# A203-V2-Expansion-Board.net
KiCad netlist of a schematic drawn in EAGLE
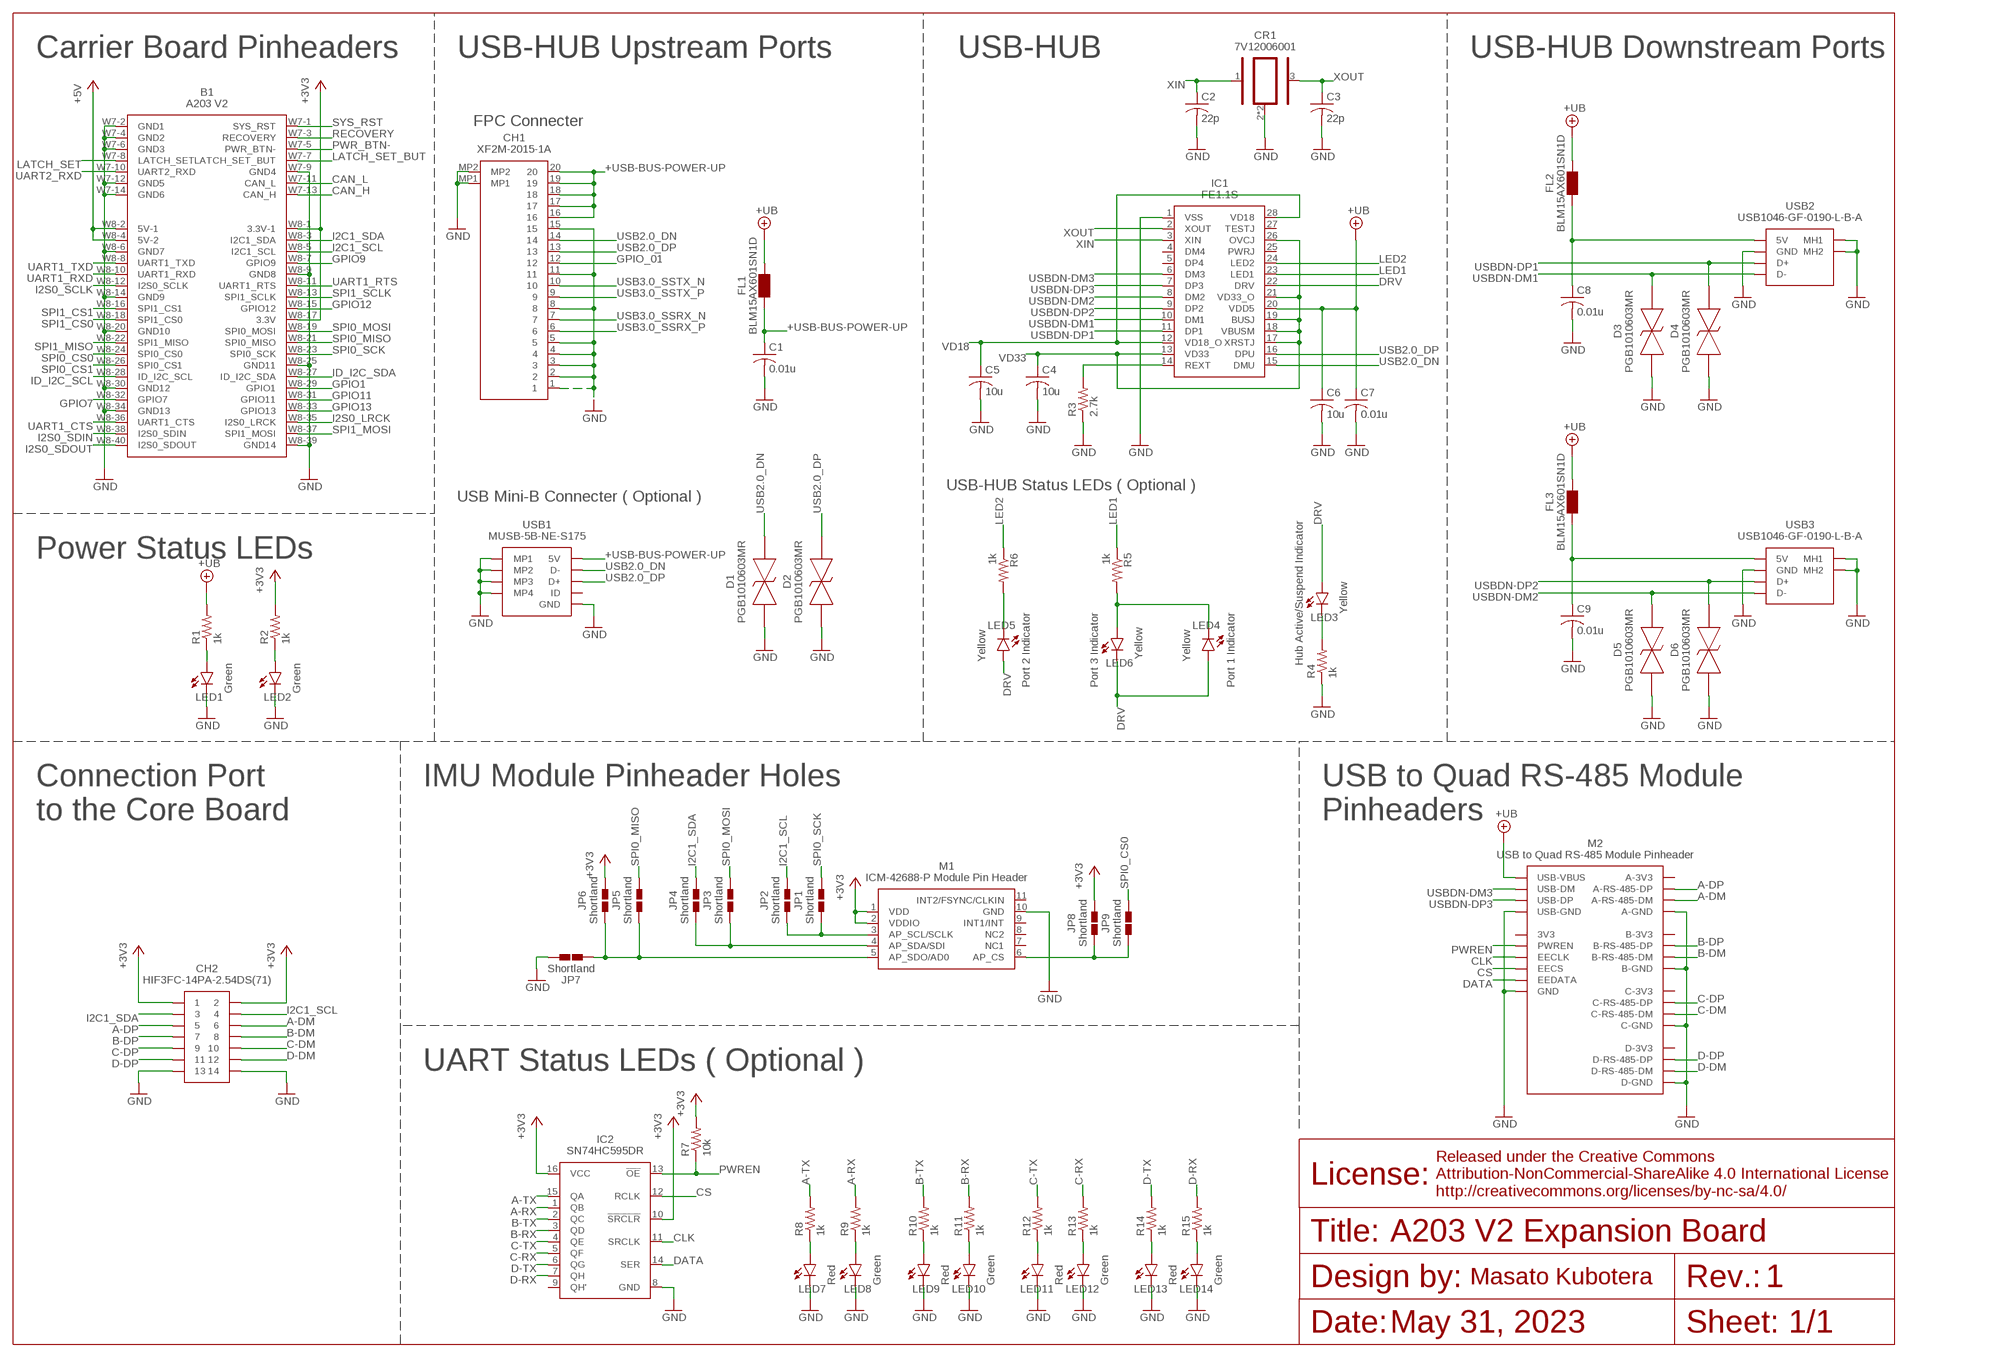
[diagram p0: schematic, sheet 1]

(export (version "E")
  (design (tool "Eeschema 10.0.6"))
  (components
    (comp (ref "B1")
      (value "SEEED_A207_V2")
      (footprint "eagle-import:SEEED_A203_V2")
      (libsource (lib "eagle-import") (part "SEEED_A207_V2"))
    )
    (comp (ref "C1")
      (value "0.01u")
      (footprint "eagle-import:C0603")
      (libsource (lib "eagle-import") (part "C-USC0603"))
    )
    (comp (ref "C2")
      (value "22p")
      (footprint "eagle-import:C0603")
      (libsource (lib "eagle-import") (part "C-USC0603"))
    )
    (comp (ref "C3")
      (value "22p")
      (footprint "eagle-import:C0603")
      (libsource (lib "eagle-import") (part "C-USC0603"))
    )
    (comp (ref "C4")
      (value "10u")
      (footprint "eagle-import:C0603")
      (libsource (lib "eagle-import") (part "C-USC0603"))
    )
    (comp (ref "C5")
      (value "10u")
      (footprint "eagle-import:C0603")
      (libsource (lib "eagle-import") (part "C-USC0603"))
    )
    (comp (ref "C6")
      (value "10u")
      (footprint "eagle-import:C0603")
      (libsource (lib "eagle-import") (part "C-USC0603"))
    )
    (comp (ref "C7")
      (value "0.01u")
      (footprint "eagle-import:C0603")
      (libsource (lib "eagle-import") (part "C-USC0603"))
    )
    (comp (ref "C8")
      (value "0.01u")
      (footprint "eagle-import:C0603")
      (libsource (lib "eagle-import") (part "C-USC0603"))
    )
    (comp (ref "C9")
      (value "0.01u")
      (footprint "eagle-import:C0603")
      (libsource (lib "eagle-import") (part "C-USC0603"))
    )
    (comp (ref "CH1")
      (value "XF2M-2015-1A")
      (footprint "eagle-import:XF2M-2015-1A")
      (libsource (lib "eagle-import") (part "XF2M-2015-1A"))
    )
    (comp (ref "CH2")
      (value "HIF3FC-14PA-2.54DS(71)")
      (footprint "eagle-import:HIF3FC-14PA-2.54DS(71)")
      (libsource (lib "eagle-import") (part "HIF3FC-14PA-2.54DS(71)"))
    )
    (comp (ref "CR1")
      (value "7V12006001")
      (footprint "eagle-import:7V12006001")
      (libsource (lib "eagle-import") (part "7V12006001"))
    )
    (comp (ref "D1")
      (value "PGB1010603MR")
      (footprint "eagle-import:0603")
      (libsource (lib "eagle-import") (part "PGB1010603MR"))
    )
    (comp (ref "D2")
      (value "PGB1010603MR")
      (footprint "eagle-import:0603")
      (libsource (lib "eagle-import") (part "PGB1010603MR"))
    )
    (comp (ref "D3")
      (value "PGB1010603MR")
      (footprint "eagle-import:0603")
      (libsource (lib "eagle-import") (part "PGB1010603MR"))
    )
    (comp (ref "D4")
      (value "PGB1010603MR")
      (footprint "eagle-import:0603")
      (libsource (lib "eagle-import") (part "PGB1010603MR"))
    )
    (comp (ref "D5")
      (value "PGB1010603MR")
      (footprint "eagle-import:0603")
      (libsource (lib "eagle-import") (part "PGB1010603MR"))
    )
    (comp (ref "D6")
      (value "PGB1010603MR")
      (footprint "eagle-import:0603")
      (libsource (lib "eagle-import") (part "PGB1010603MR"))
    )
    (comp (ref "FL1")
      (value "BLM15AX601SN1D")
      (footprint "eagle-import:BLM15AX601SN1D")
      (libsource (lib "eagle-import") (part "BLM15AX601SN1D"))
    )
    (comp (ref "FL2")
      (value "BLM15AX601SN1D")
      (footprint "eagle-import:BLM15AX601SN1D")
      (libsource (lib "eagle-import") (part "BLM15AX601SN1D"))
    )
    (comp (ref "FL3")
      (value "BLM15AX601SN1D")
      (footprint "eagle-import:BLM15AX601SN1D")
      (libsource (lib "eagle-import") (part "BLM15AX601SN1D"))
    )
    (comp (ref "IC1")
      (value "FE1.1S")
      (footprint "eagle-import:FE1.1S")
      (libsource (lib "eagle-import") (part "FE1.1S"))
    )
    (comp (ref "IC2")
      (value "SN74HC595DR")
      (footprint "eagle-import:SOIC-16")
      (libsource (lib "eagle-import") (part "SN74HC595DR"))
    )
    (comp (ref "JP1")
      (value "SHORTLAND")
      (footprint "eagle-import:SHORTLAND")
      (libsource (lib "eagle-import") (part "SHORTLAND"))
    )
    (comp (ref "JP2")
      (value "SHORTLAND")
      (footprint "eagle-import:SHORTLAND")
      (libsource (lib "eagle-import") (part "SHORTLAND"))
    )
    (comp (ref "JP3")
      (value "SHORTLAND")
      (footprint "eagle-import:SHORTLAND")
      (libsource (lib "eagle-import") (part "SHORTLAND"))
    )
    (comp (ref "JP4")
      (value "SHORTLAND")
      (footprint "eagle-import:SHORTLAND")
      (libsource (lib "eagle-import") (part "SHORTLAND"))
    )
    (comp (ref "JP5")
      (value "SHORTLAND")
      (footprint "eagle-import:SHORTLAND")
      (libsource (lib "eagle-import") (part "SHORTLAND"))
    )
    (comp (ref "JP6")
      (value "SHORTLAND")
      (footprint "eagle-import:SHORTLAND")
      (libsource (lib "eagle-import") (part "SHORTLAND"))
    )
    (comp (ref "JP7")
      (value "SHORTLAND")
      (footprint "eagle-import:SHORTLAND")
      (libsource (lib "eagle-import") (part "SHORTLAND"))
    )
    (comp (ref "JP8")
      (value "SHORTLAND")
      (footprint "eagle-import:SHORTLAND")
      (libsource (lib "eagle-import") (part "SHORTLAND"))
    )
    (comp (ref "JP9")
      (value "SHORTLAND")
      (footprint "eagle-import:SHORTLAND")
      (libsource (lib "eagle-import") (part "SHORTLAND"))
    )
    (comp (ref "LED1")
      (value "Green")
      (footprint "eagle-import:SML0603")
      (libsource (lib "eagle-import") (part "LEDSML0603"))
    )
    (comp (ref "LED2")
      (value "Green")
      (footprint "eagle-import:SML0603")
      (libsource (lib "eagle-import") (part "LEDSML0603"))
    )
    (comp (ref "LED3")
      (value "Yellow")
      (footprint "eagle-import:SML0603")
      (libsource (lib "eagle-import") (part "LEDSML0603"))
    )
    (comp (ref "LED4")
      (value "Yellow")
      (footprint "eagle-import:SML0603")
      (libsource (lib "eagle-import") (part "LEDSML0603"))
    )
    (comp (ref "LED5")
      (value "Yellow")
      (footprint "eagle-import:SML0603")
      (libsource (lib "eagle-import") (part "LEDSML0603"))
    )
    (comp (ref "LED6")
      (value "Yellow")
      (footprint "eagle-import:SML0603")
      (libsource (lib "eagle-import") (part "LEDSML0603"))
    )
    (comp (ref "LED7")
      (value "Red")
      (footprint "eagle-import:SML0603")
      (libsource (lib "eagle-import") (part "LEDSML0603"))
    )
    (comp (ref "LED8")
      (value "Green")
      (footprint "eagle-import:SML0603")
      (libsource (lib "eagle-import") (part "LEDSML0603"))
    )
    (comp (ref "LED9")
      (value "Red")
      (footprint "eagle-import:SML0603")
      (libsource (lib "eagle-import") (part "LEDSML0603"))
    )
    (comp (ref "LED10")
      (value "Green")
      (footprint "eagle-import:SML0603")
      (libsource (lib "eagle-import") (part "LEDSML0603"))
    )
    (comp (ref "LED11")
      (value "Red")
      (footprint "eagle-import:SML0603")
      (libsource (lib "eagle-import") (part "LEDSML0603"))
    )
    (comp (ref "LED12")
      (value "Green")
      (footprint "eagle-import:SML0603")
      (libsource (lib "eagle-import") (part "LEDSML0603"))
    )
    (comp (ref "LED13")
      (value "Red")
      (footprint "eagle-import:SML0603")
      (libsource (lib "eagle-import") (part "LEDSML0603"))
    )
    (comp (ref "LED14")
      (value "Green")
      (footprint "eagle-import:SML0603")
      (libsource (lib "eagle-import") (part "LEDSML0603"))
    )
    (comp (ref "M1")
      (value "ICM-42688-P-MODULE-PINHEADER")
      (footprint "eagle-import:ICM-42688-P-MODULE-PINHEADER")
      (libsource (lib "eagle-import") (part "ICM-42688-P-MODULE-PINHEADER"))
    )
    (comp (ref "M2")
      (value "USB-TO-QUAD-RS-485-CONV-MODULET-PLACE")
      (footprint "eagle-import:USB-TO-QUAD-RS-485-CONV-MODULE-SILK")
      (libsource (lib "eagle-import") (part "USB-TO-QUAD-RS-485-CONV-MODULET-PLACE"))
    )
    (comp (ref "R1")
      (value "1k")
      (footprint "eagle-import:R0603")
      (libsource (lib "eagle-import") (part "R-US_R0603"))
    )
    (comp (ref "R2")
      (value "1k")
      (footprint "eagle-import:R0603")
      (libsource (lib "eagle-import") (part "R-US_R0603"))
    )
    (comp (ref "R3")
      (value "2.7k")
      (footprint "eagle-import:R0603")
      (libsource (lib "eagle-import") (part "R-US_R0603"))
    )
    (comp (ref "R4")
      (value "1k")
      (footprint "eagle-import:R0603")
      (libsource (lib "eagle-import") (part "R-US_R0603"))
    )
    (comp (ref "R5")
      (value "1k")
      (footprint "eagle-import:R0603")
      (libsource (lib "eagle-import") (part "R-US_R0603"))
    )
    (comp (ref "R6")
      (value "1k")
      (footprint "eagle-import:R0603")
      (libsource (lib "eagle-import") (part "R-US_R0603"))
    )
    (comp (ref "R7")
      (value "10k")
      (footprint "eagle-import:R0603")
      (libsource (lib "eagle-import") (part "R-US_R0603"))
    )
    (comp (ref "R8")
      (value "1k")
      (footprint "eagle-import:R0603")
      (libsource (lib "eagle-import") (part "R-US_R0603"))
    )
    (comp (ref "R9")
      (value "1k")
      (footprint "eagle-import:R0603")
      (libsource (lib "eagle-import") (part "R-US_R0603"))
    )
    (comp (ref "R10")
      (value "1k")
      (footprint "eagle-import:R0603")
      (libsource (lib "eagle-import") (part "R-US_R0603"))
    )
    (comp (ref "R11")
      (value "1k")
      (footprint "eagle-import:R0603")
      (libsource (lib "eagle-import") (part "R-US_R0603"))
    )
    (comp (ref "R12")
      (value "1k")
      (footprint "eagle-import:R0603")
      (libsource (lib "eagle-import") (part "R-US_R0603"))
    )
    (comp (ref "R13")
      (value "1k")
      (footprint "eagle-import:R0603")
      (libsource (lib "eagle-import") (part "R-US_R0603"))
    )
    (comp (ref "R14")
      (value "1k")
      (footprint "eagle-import:R0603")
      (libsource (lib "eagle-import") (part "R-US_R0603"))
    )
    (comp (ref "R15")
      (value "1k")
      (footprint "eagle-import:R0603")
      (libsource (lib "eagle-import") (part "R-US_R0603"))
    )
    (comp (ref "USB1")
      (value "MINI_USB_B_SMD")
      (footprint "eagle-import:MINI_USB_B_SMD")
      (libsource (lib "eagle-import") (part "MINI_USB_B_SMD"))
    )
    (comp (ref "USB2")
      (value "USB_A_X1_SMD")
      (footprint "eagle-import:USB_A_X1_SMD")
      (libsource (lib "eagle-import") (part "USB_A_X1_SMD"))
    )
    (comp (ref "USB3")
      (value "USB_A_X1_SMD")
      (footprint "eagle-import:USB_A_X1_SMD")
      (libsource (lib "eagle-import") (part "USB_A_X1_SMD"))
    )
  )
  (nets
    (net (code "1") (name "+3V3") (class "Default")
      (node (ref "B1") (pin "W8-1") (pinfunction "3.3V-1_W8-1") (pintype "bidirectional"))
      (node (ref "B1") (pin "W8-17") (pinfunction "3.3V_W8-17") (pintype "bidirectional"))
      (node (ref "CH2") (pin "1") (pinfunction "1_1") (pintype "bidirectional"))
      (node (ref "CH2") (pin "2") (pinfunction "2_2") (pintype "bidirectional"))
      (node (ref "IC2") (pin "10") (pinfunction "~{SRCLR}_10") (pintype "bidirectional"))
      (node (ref "IC2") (pin "16") (pinfunction "VCC_16") (pintype "bidirectional"))
      (node (ref "JP6") (pin "2") (pinfunction "2_2") (pintype "bidirectional"))
      (node (ref "JP8") (pin "2") (pinfunction "2_2") (pintype "bidirectional"))
      (node (ref "M1") (pin "1") (pinfunction "VDD_1") (pintype "bidirectional"))
      (node (ref "M1") (pin "2") (pinfunction "VDDIO_2") (pintype "bidirectional"))
      (node (ref "R2") (pin "2") (pinfunction "2_2") (pintype "passive"))
      (node (ref "R7") (pin "2") (pinfunction "2_2") (pintype "passive"))
    )
    (net (code "2") (name "+5V") (class "Default")
      (node (ref "B1") (pin "W8-2") (pinfunction "5V-1_W8-2") (pintype "bidirectional"))
      (node (ref "B1") (pin "W8-4") (pinfunction "5V-2_W8-4") (pintype "bidirectional"))
    )
    (net (code "3") (name "+UB") (class "Default")
      (node (ref "C6") (pin "1") (pinfunction "1_1") (pintype "passive"))
      (node (ref "C7") (pin "1") (pinfunction "1_1") (pintype "passive"))
      (node (ref "FL1") (pin "2") (pinfunction "2_2") (pintype "bidirectional"))
      (node (ref "FL2") (pin "2") (pinfunction "2_2") (pintype "bidirectional"))
      (node (ref "FL3") (pin "2") (pinfunction "2_2") (pintype "bidirectional"))
      (node (ref "IC1") (pin "20") (pinfunction "VDD5_20") (pintype "bidirectional"))
      (node (ref "M2") (pin "USB-VBUS") (pinfunction "USB-VBUS_USB-VBUS") (pintype "bidirectional"))
      (node (ref "R1") (pin "2") (pinfunction "2_2") (pintype "passive"))
    )
    (net (code "4") (name "/+USB-BUS-POWER-UP") (class "Default")
      (node (ref "C1") (pin "1") (pinfunction "1_1") (pintype "passive"))
      (node (ref "CH1") (pin "16") (pinfunction "16_16") (pintype "bidirectional"))
      (node (ref "CH1") (pin "17") (pinfunction "17_17") (pintype "bidirectional"))
      (node (ref "CH1") (pin "18") (pinfunction "18_18") (pintype "bidirectional"))
      (node (ref "CH1") (pin "19") (pinfunction "19_19") (pintype "bidirectional"))
      (node (ref "CH1") (pin "20") (pinfunction "20_20") (pintype "bidirectional"))
      (node (ref "FL1") (pin "1") (pinfunction "1_1") (pintype "bidirectional"))
      (node (ref "USB1") (pin "1") (pinfunction "5V_1") (pintype "bidirectional"))
    )
    (net (code "5") (name "/A-DM") (class "Default")
      (node (ref "CH2") (pin "6") (pinfunction "6_6") (pintype "bidirectional"))
      (node (ref "M2") (pin "A-RS-485-DM") (pinfunction "A-RS-485-DM_A-RS-485-DM") (pintype "bidirectional"))
    )
    (net (code "6") (name "/A-DP") (class "Default")
      (node (ref "CH2") (pin "5") (pinfunction "5_5") (pintype "bidirectional"))
      (node (ref "M2") (pin "A-RS-485-DP") (pinfunction "A-RS-485-DP_A-RS-485-DP") (pintype "bidirectional"))
    )
    (net (code "7") (name "/A-RX") (class "Default")
      (node (ref "IC2") (pin "1") (pinfunction "QB_1") (pintype "bidirectional"))
      (node (ref "R9") (pin "2") (pinfunction "2_2") (pintype "passive"))
    )
    (net (code "8") (name "/A-TX") (class "Default")
      (node (ref "IC2") (pin "15") (pinfunction "QA_15") (pintype "bidirectional"))
      (node (ref "R8") (pin "2") (pinfunction "2_2") (pintype "passive"))
    )
    (net (code "9") (name "/B-DM") (class "Default")
      (node (ref "CH2") (pin "8") (pinfunction "8_8") (pintype "bidirectional"))
      (node (ref "M2") (pin "B-RS-485-DM") (pinfunction "B-RS-485-DM_B-RS-485-DM") (pintype "bidirectional"))
    )
    (net (code "10") (name "/B-DP") (class "Default")
      (node (ref "CH2") (pin "7") (pinfunction "7_7") (pintype "bidirectional"))
      (node (ref "M2") (pin "B-RS-485-DP") (pinfunction "B-RS-485-DP_B-RS-485-DP") (pintype "bidirectional"))
    )
    (net (code "11") (name "/B-RX") (class "Default")
      (node (ref "IC2") (pin "3") (pinfunction "QD_3") (pintype "bidirectional"))
      (node (ref "R11") (pin "2") (pinfunction "2_2") (pintype "passive"))
    )
    (net (code "12") (name "/B-TX") (class "Default")
      (node (ref "IC2") (pin "2") (pinfunction "QC_2") (pintype "bidirectional"))
      (node (ref "R10") (pin "2") (pinfunction "2_2") (pintype "passive"))
    )
    (net (code "13") (name "/C-DM") (class "Default")
      (node (ref "CH2") (pin "10") (pinfunction "10_10") (pintype "bidirectional"))
      (node (ref "M2") (pin "C-RS-485-DM") (pinfunction "C-RS-485-DM_C-RS-485-DM") (pintype "bidirectional"))
    )
    (net (code "14") (name "/C-DP") (class "Default")
      (node (ref "CH2") (pin "9") (pinfunction "9_9") (pintype "bidirectional"))
      (node (ref "M2") (pin "C-RS-485-DP") (pinfunction "C-RS-485-DP_C-RS-485-DP") (pintype "bidirectional"))
    )
    (net (code "15") (name "/C-RX") (class "Default")
      (node (ref "IC2") (pin "5") (pinfunction "QF_5") (pintype "bidirectional"))
      (node (ref "R13") (pin "2") (pinfunction "2_2") (pintype "passive"))
    )
    (net (code "16") (name "/C-TX") (class "Default")
      (node (ref "IC2") (pin "4") (pinfunction "QE_4") (pintype "bidirectional"))
      (node (ref "R12") (pin "2") (pinfunction "2_2") (pintype "passive"))
    )
    (net (code "17") (name "/CAN_H") (class "Default")
      (node (ref "B1") (pin "W7-13") (pinfunction "CAN_H_W7-13") (pintype "bidirectional"))
    )
    (net (code "18") (name "/CAN_L") (class "Default")
      (node (ref "B1") (pin "W7-11") (pinfunction "CAN_L_W7-11") (pintype "bidirectional"))
    )
    (net (code "19") (name "/CLK") (class "Default")
      (node (ref "IC2") (pin "11") (pinfunction "SRCLK_11") (pintype "bidirectional"))
      (node (ref "M2") (pin "EECLK") (pinfunction "EECLK_EECLK") (pintype "bidirectional"))
    )
    (net (code "20") (name "/CS") (class "Default")
      (node (ref "IC2") (pin "12") (pinfunction "RCLK_12") (pintype "bidirectional"))
      (node (ref "M2") (pin "EECS") (pinfunction "EECS_EECS") (pintype "bidirectional"))
    )
    (net (code "21") (name "/D-DM") (class "Default")
      (node (ref "CH2") (pin "12") (pinfunction "12_12") (pintype "bidirectional"))
      (node (ref "M2") (pin "D-RS-485-DM") (pinfunction "D-RS-485-DM_D-RS-485-DM") (pintype "bidirectional"))
    )
    (net (code "22") (name "/D-DP") (class "Default")
      (node (ref "CH2") (pin "11") (pinfunction "11_11") (pintype "bidirectional"))
      (node (ref "M2") (pin "D-RS-485-DP") (pinfunction "D-RS-485-DP_D-RS-485-DP") (pintype "bidirectional"))
    )
    (net (code "23") (name "/D-RX") (class "Default")
      (node (ref "IC2") (pin "7") (pinfunction "QH_7") (pintype "bidirectional"))
      (node (ref "R15") (pin "2") (pinfunction "2_2") (pintype "passive"))
    )
    (net (code "24") (name "/D-TX") (class "Default")
      (node (ref "IC2") (pin "6") (pinfunction "QG_6") (pintype "bidirectional"))
      (node (ref "R14") (pin "2") (pinfunction "2_2") (pintype "passive"))
    )
    (net (code "25") (name "/DATA") (class "Default")
      (node (ref "IC2") (pin "14") (pinfunction "SER_14") (pintype "bidirectional"))
      (node (ref "M2") (pin "EEDATA") (pinfunction "EEDATA_EEDATA") (pintype "bidirectional"))
    )
    (net (code "26") (name "/DRV") (class "Default")
      (node (ref "IC1") (pin "22") (pinfunction "DRV_22") (pintype "bidirectional"))
      (node (ref "LED3") (pin "A") (pinfunction "A_A") (pintype "passive"))
      (node (ref "LED4") (pin "A") (pinfunction "A_A") (pintype "passive"))
      (node (ref "LED5") (pin "A") (pinfunction "A_A") (pintype "passive"))
      (node (ref "LED6") (pin "C") (pinfunction "C_C") (pintype "passive"))
    )
    (net (code "27") (name "/GPIO1") (class "Default")
      (node (ref "B1") (pin "W8-29") (pinfunction "GPIO1_W8-29") (pintype "bidirectional"))
    )
    (net (code "28") (name "/GPIO7") (class "Default")
      (node (ref "B1") (pin "W8-32") (pinfunction "GPIO7_W8-32") (pintype "bidirectional"))
    )
    (net (code "29") (name "/GPIO9") (class "Default")
      (node (ref "B1") (pin "W8-7") (pinfunction "GPIO9_W8-7") (pintype "bidirectional"))
    )
    (net (code "30") (name "/GPIO11") (class "Default")
      (node (ref "B1") (pin "W8-31") (pinfunction "GPIO11_W8-31") (pintype "bidirectional"))
    )
    (net (code "31") (name "/GPIO12") (class "Default")
      (node (ref "B1") (pin "W8-15") (pinfunction "GPIO12_W8-15") (pintype "bidirectional"))
    )
    (net (code "32") (name "/GPIO13") (class "Default")
      (node (ref "B1") (pin "W8-33") (pinfunction "GPIO13_W8-33") (pintype "bidirectional"))
    )
    (net (code "33") (name "/GPIO_01") (class "Default")
      (node (ref "CH1") (pin "12") (pinfunction "12_12") (pintype "bidirectional"))
    )
    (net (code "34") (name "/I2C1_SCL") (class "Default")
      (node (ref "B1") (pin "W8-5") (pinfunction "I2C1_SCL_W8-5") (pintype "bidirectional"))
      (node (ref "CH2") (pin "4") (pinfunction "4_4") (pintype "bidirectional"))
      (node (ref "JP2") (pin "2") (pinfunction "2_2") (pintype "bidirectional"))
    )
    (net (code "35") (name "/I2C1_SDA") (class "Default")
      (node (ref "B1") (pin "W8-3") (pinfunction "I2C1_SDA_W8-3") (pintype "bidirectional"))
      (node (ref "CH2") (pin "3") (pinfunction "3_3") (pintype "bidirectional"))
      (node (ref "JP4") (pin "2") (pinfunction "2_2") (pintype "bidirectional"))
    )
    (net (code "36") (name "/I2S0_LRCK") (class "Default")
      (node (ref "B1") (pin "W8-35") (pinfunction "I2S0_LRCK_W8-35") (pintype "bidirectional"))
    )
    (net (code "37") (name "/I2S0_SCLK") (class "Default")
      (node (ref "B1") (pin "W8-12") (pinfunction "I2S0_SCLK_W8-12") (pintype "bidirectional"))
    )
    (net (code "38") (name "/I2S0_SDIN") (class "Default")
      (node (ref "B1") (pin "W8-38") (pinfunction "I2S0_SDIN_W8-38") (pintype "bidirectional"))
    )
    (net (code "39") (name "/I2S0_SDOUT") (class "Default")
      (node (ref "B1") (pin "W8-40") (pinfunction "I2S0_SDOUT_W8-40") (pintype "bidirectional"))
    )
    (net (code "40") (name "/ID_I2C_SCL") (class "Default")
      (node (ref "B1") (pin "W8-28") (pinfunction "ID_I2C_SCL_W8-28") (pintype "bidirectional"))
    )
    (net (code "41") (name "/ID_I2C_SDA") (class "Default")
      (node (ref "B1") (pin "W8-27") (pinfunction "ID_I2C_SDA_W8-27") (pintype "bidirectional"))
    )
    (net (code "42") (name "/LATCH_SET") (class "Default")
      (node (ref "B1") (pin "W7-8") (pinfunction "LATCH_SET_W7-8") (pintype "bidirectional"))
    )
    (net (code "43") (name "/LATCH_SET_BUT") (class "Default")
      (node (ref "B1") (pin "W7-7") (pinfunction "LATCH_SET_BUT_W7-7") (pintype "bidirectional"))
    )
    (net (code "44") (name "/LED1") (class "Default")
      (node (ref "IC1") (pin "23") (pinfunction "LED1_23") (pintype "bidirectional"))
      (node (ref "R5") (pin "1") (pinfunction "1_1") (pintype "passive"))
    )
    (net (code "45") (name "/LED2") (class "Default")
      (node (ref "IC1") (pin "24") (pinfunction "LED2_24") (pintype "bidirectional"))
      (node (ref "R6") (pin "1") (pinfunction "1_1") (pintype "passive"))
    )
    (net (code "46") (name "/PWREN") (class "Default")
      (node (ref "IC2") (pin "13") (pinfunction "~{OE}_13") (pintype "bidirectional"))
      (node (ref "M2") (pin "PWREN") (pinfunction "PWREN_PWREN") (pintype "bidirectional"))
      (node (ref "R7") (pin "1") (pinfunction "1_1") (pintype "passive"))
    )
    (net (code "47") (name "/PWR_BTN-") (class "Default")
      (node (ref "B1") (pin "W7-5") (pinfunction "PWR_BTN-_W7-5") (pintype "bidirectional"))
    )
    (net (code "48") (name "/RECOVERY") (class "Default")
      (node (ref "B1") (pin "W7-3") (pinfunction "RECOVERY_W7-3") (pintype "bidirectional"))
    )
    (net (code "49") (name "/SPI0_CS0") (class "Default")
      (node (ref "B1") (pin "W8-24") (pinfunction "SPI0_CS0_W8-24") (pintype "bidirectional"))
      (node (ref "JP9") (pin "2") (pinfunction "2_2") (pintype "bidirectional"))
    )
    (net (code "50") (name "/SPI0_CS1") (class "Default")
      (node (ref "B1") (pin "W8-26") (pinfunction "SPI0_CS1_W8-26") (pintype "bidirectional"))
    )
    (net (code "51") (name "/SPI0_MISO") (class "Default")
      (node (ref "B1") (pin "W8-21") (pinfunction "SPI0_MISO_W8-21") (pintype "bidirectional"))
      (node (ref "JP5") (pin "2") (pinfunction "2_2") (pintype "bidirectional"))
    )
    (net (code "52") (name "/SPI0_MOSI") (class "Default")
      (node (ref "B1") (pin "W8-19") (pinfunction "SPI0_MOSI_W8-19") (pintype "bidirectional"))
      (node (ref "JP3") (pin "2") (pinfunction "2_2") (pintype "bidirectional"))
    )
    (net (code "53") (name "/SPI0_SCK") (class "Default")
      (node (ref "B1") (pin "W8-23") (pinfunction "SPI0_SCK_W8-23") (pintype "bidirectional"))
      (node (ref "JP1") (pin "2") (pinfunction "2_2") (pintype "bidirectional"))
    )
    (net (code "54") (name "/SPI1_CS0") (class "Default")
      (node (ref "B1") (pin "W8-18") (pinfunction "SPI1_CS0_W8-18") (pintype "bidirectional"))
    )
    (net (code "55") (name "/SPI1_CS1") (class "Default")
      (node (ref "B1") (pin "W8-16") (pinfunction "SPI1_CS1_W8-16") (pintype "bidirectional"))
    )
    (net (code "56") (name "/SPI1_MISO") (class "Default")
      (node (ref "B1") (pin "W8-22") (pinfunction "SPI1_MISO_W8-22") (pintype "bidirectional"))
    )
    (net (code "57") (name "/SPI1_MOSI") (class "Default")
      (node (ref "B1") (pin "W8-37") (pinfunction "SPI1_MOSI_W8-37") (pintype "bidirectional"))
    )
    (net (code "58") (name "/SPI1_SCLK") (class "Default")
      (node (ref "B1") (pin "W8-13") (pinfunction "SPI1_SCLK_W8-13") (pintype "bidirectional"))
    )
    (net (code "59") (name "/SYS_RST") (class "Default")
      (node (ref "B1") (pin "W7-1") (pinfunction "SYS_RST_W7-1") (pintype "bidirectional"))
    )
    (net (code "60") (name "/UART1_CTS") (class "Default")
      (node (ref "B1") (pin "W8-36") (pinfunction "UART1_CTS_W8-36") (pintype "bidirectional"))
    )
    (net (code "61") (name "/UART1_RTS") (class "Default")
      (node (ref "B1") (pin "W8-11") (pinfunction "UART1_RTS_W8-11") (pintype "bidirectional"))
    )
    (net (code "62") (name "/UART1_RXD") (class "Default")
      (node (ref "B1") (pin "W8-10") (pinfunction "UART1_RXD_W8-10") (pintype "bidirectional"))
    )
    (net (code "63") (name "/UART1_TXD") (class "Default")
      (node (ref "B1") (pin "W8-8") (pinfunction "UART1_TXD_W8-8") (pintype "bidirectional"))
    )
    (net (code "64") (name "/UART2_RXD") (class "Default")
      (node (ref "B1") (pin "W7-10") (pinfunction "UART2_RXD_W7-10") (pintype "bidirectional"))
    )
    (net (code "65") (name "/USB2.0_DN") (class "Default")
      (node (ref "CH1") (pin "14") (pinfunction "14_14") (pintype "bidirectional"))
      (node (ref "D1") (pin "2") (pinfunction "2_2") (pintype "bidirectional"))
      (node (ref "IC1") (pin "15") (pinfunction "DMU_15") (pintype "bidirectional"))
      (node (ref "USB1") (pin "2") (pinfunction "D-_2") (pintype "bidirectional"))
    )
    (net (code "66") (name "/USB2.0_DP") (class "Default")
      (node (ref "CH1") (pin "13") (pinfunction "13_13") (pintype "bidirectional"))
      (node (ref "D2") (pin "2") (pinfunction "2_2") (pintype "bidirectional"))
      (node (ref "IC1") (pin "16") (pinfunction "DPU_16") (pintype "bidirectional"))
      (node (ref "USB1") (pin "3") (pinfunction "D+_3") (pintype "bidirectional"))
    )
    (net (code "67") (name "/USB3.0_SSRX_N") (class "Default")
      (node (ref "CH1") (pin "7") (pinfunction "7_7") (pintype "bidirectional"))
    )
    (net (code "68") (name "/USB3.0_SSRX_P") (class "Default")
      (node (ref "CH1") (pin "6") (pinfunction "6_6") (pintype "bidirectional"))
    )
    (net (code "69") (name "/USB3.0_SSTX_N") (class "Default")
      (node (ref "CH1") (pin "10") (pinfunction "10_10") (pintype "bidirectional"))
    )
    (net (code "70") (name "/USB3.0_SSTX_P") (class "Default")
      (node (ref "CH1") (pin "9") (pinfunction "9_9") (pintype "bidirectional"))
    )
    (net (code "71") (name "/USBDN-DM1") (class "Default")
      (node (ref "D3") (pin "2") (pinfunction "2_2") (pintype "bidirectional"))
      (node (ref "IC1") (pin "10") (pinfunction "DM1_10") (pintype "bidirectional"))
      (node (ref "USB2") (pin "2") (pinfunction "D-_2") (pintype "bidirectional"))
    )
    (net (code "72") (name "/USBDN-DM2") (class "Default")
      (node (ref "D5") (pin "2") (pinfunction "2_2") (pintype "bidirectional"))
      (node (ref "IC1") (pin "8") (pinfunction "DM2_8") (pintype "bidirectional"))
      (node (ref "USB3") (pin "2") (pinfunction "D-_2") (pintype "bidirectional"))
    )
    (net (code "73") (name "/USBDN-DM3") (class "Default")
      (node (ref "IC1") (pin "6") (pinfunction "DM3_6") (pintype "bidirectional"))
      (node (ref "M2") (pin "USB-DM") (pinfunction "USB-DM_USB-DM") (pintype "bidirectional"))
    )
    (net (code "74") (name "/USBDN-DP1") (class "Default")
      (node (ref "D4") (pin "2") (pinfunction "2_2") (pintype "bidirectional"))
      (node (ref "IC1") (pin "11") (pinfunction "DP1_11") (pintype "bidirectional"))
      (node (ref "USB2") (pin "3") (pinfunction "D+_3") (pintype "bidirectional"))
    )
    (net (code "75") (name "/USBDN-DP2") (class "Default")
      (node (ref "D6") (pin "2") (pinfunction "2_2") (pintype "bidirectional"))
      (node (ref "IC1") (pin "9") (pinfunction "DP2_9") (pintype "bidirectional"))
      (node (ref "USB3") (pin "3") (pinfunction "D+_3") (pintype "bidirectional"))
    )
    (net (code "76") (name "/USBDN-DP3") (class "Default")
      (node (ref "IC1") (pin "7") (pinfunction "DP3_7") (pintype "bidirectional"))
      (node (ref "M2") (pin "USB-DP") (pinfunction "USB-DP_USB-DP") (pintype "bidirectional"))
    )
    (net (code "77") (name "/VD18") (class "Default")
      (node (ref "C5") (pin "1") (pinfunction "1_1") (pintype "passive"))
      (node (ref "IC1") (pin "12") (pinfunction "VD18_O_12") (pintype "bidirectional"))
      (node (ref "IC1") (pin "28") (pinfunction "VD18_28") (pintype "bidirectional"))
    )
    (net (code "78") (name "/VD33") (class "Default")
      (node (ref "C4") (pin "1") (pinfunction "1_1") (pintype "passive"))
      (node (ref "IC1") (pin "13") (pinfunction "VD33_13") (pintype "bidirectional"))
      (node (ref "IC1") (pin "17") (pinfunction "XRSTJ_17") (pintype "bidirectional"))
      (node (ref "IC1") (pin "18") (pinfunction "VBUSM_18") (pintype "bidirectional"))
      (node (ref "IC1") (pin "19") (pinfunction "BUSJ_19") (pintype "bidirectional"))
      (node (ref "IC1") (pin "21") (pinfunction "VD33_O_21") (pintype "bidirectional"))
      (node (ref "IC1") (pin "26") (pinfunction "OVCJ_26") (pintype "bidirectional"))
    )
    (net (code "79") (name "/XIN") (class "Default")
      (node (ref "C2") (pin "1") (pinfunction "1_1") (pintype "passive"))
      (node (ref "CR1") (pin "1") (pinfunction "P$1_1") (pintype "bidirectional"))
      (node (ref "IC1") (pin "3") (pinfunction "XIN_3") (pintype "bidirectional"))
    )
    (net (code "80") (name "/XOUT") (class "Default")
      (node (ref "C3") (pin "1") (pinfunction "1_1") (pintype "passive"))
      (node (ref "CR1") (pin "3") (pinfunction "P$2_3") (pintype "bidirectional"))
      (node (ref "IC1") (pin "2") (pinfunction "XOUT_2") (pintype "bidirectional"))
    )
    (net (code "81") (name "GND") (class "Default")
      (node (ref "B1") (pin "W7-12") (pinfunction "GND5_W7-12") (pintype "bidirectional"))
      (node (ref "B1") (pin "W7-14") (pinfunction "GND6_W7-14") (pintype "bidirectional"))
      (node (ref "B1") (pin "W7-2") (pinfunction "GND1_W7-2") (pintype "bidirectional"))
      (node (ref "B1") (pin "W7-4") (pinfunction "GND2_W7-4") (pintype "bidirectional"))
      (node (ref "B1") (pin "W7-6") (pinfunction "GND3_W7-6") (pintype "bidirectional"))
      (node (ref "B1") (pin "W7-9") (pinfunction "GND4_W7-9") (pintype "bidirectional"))
      (node (ref "B1") (pin "W8-14") (pinfunction "GND9_W8-14") (pintype "bidirectional"))
      (node (ref "B1") (pin "W8-20") (pinfunction "GND10_W8-20") (pintype "bidirectional"))
      (node (ref "B1") (pin "W8-25") (pinfunction "GND11_W8-25") (pintype "bidirectional"))
      (node (ref "B1") (pin "W8-30") (pinfunction "GND12_W8-30") (pintype "bidirectional"))
      (node (ref "B1") (pin "W8-34") (pinfunction "GND13_W8-34") (pintype "bidirectional"))
      (node (ref "B1") (pin "W8-39") (pinfunction "GND14_W8-39") (pintype "bidirectional"))
      (node (ref "B1") (pin "W8-6") (pinfunction "GND7_W8-6") (pintype "bidirectional"))
      (node (ref "B1") (pin "W8-9") (pinfunction "GND8_W8-9") (pintype "bidirectional"))
      (node (ref "C1") (pin "2") (pinfunction "2_2") (pintype "passive"))
      (node (ref "C2") (pin "2") (pinfunction "2_2") (pintype "passive"))
      (node (ref "C3") (pin "2") (pinfunction "2_2") (pintype "passive"))
      (node (ref "C4") (pin "2") (pinfunction "2_2") (pintype "passive"))
      (node (ref "C5") (pin "2") (pinfunction "2_2") (pintype "passive"))
      (node (ref "C6") (pin "2") (pinfunction "2_2") (pintype "passive"))
      (node (ref "C7") (pin "2") (pinfunction "2_2") (pintype "passive"))
      (node (ref "C8") (pin "2") (pinfunction "2_2") (pintype "passive"))
      (node (ref "C9") (pin "2") (pinfunction "2_2") (pintype "passive"))
      (node (ref "CH1") (pin "1") (pinfunction "1_1") (pintype "bidirectional"))
      (node (ref "CH1") (pin "11") (pinfunction "11_11") (pintype "bidirectional"))
      (node (ref "CH1") (pin "15") (pinfunction "15_15") (pintype "bidirectional"))
      (node (ref "CH1") (pin "2") (pinfunction "2_2") (pintype "bidirectional"))
      (node (ref "CH1") (pin "3") (pinfunction "3_3") (pintype "bidirectional"))
      (node (ref "CH1") (pin "4") (pinfunction "4_4") (pintype "bidirectional"))
      (node (ref "CH1") (pin "5") (pinfunction "5_5") (pintype "bidirectional"))
      (node (ref "CH1") (pin "8") (pinfunction "8_8") (pintype "bidirectional"))
      (node (ref "CH1") (pin "MP1") (pinfunction "MP1_MP1") (pintype "bidirectional"))
      (node (ref "CH1") (pin "MP2") (pinfunction "MP2_MP2") (pintype "bidirectional"))
      (node (ref "CH2") (pin "13") (pinfunction "13_13") (pintype "bidirectional"))
      (node (ref "CH2") (pin "14") (pinfunction "14_14") (pintype "bidirectional"))
      (node (ref "CR1") (pin "2") (pinfunction "P$3_2") (pintype "bidirectional"))
      (node (ref "CR1") (pin "4") (pinfunction "P$3_4") (pintype "bidirectional"))
      (node (ref "D1") (pin "1") (pinfunction "1_1") (pintype "bidirectional"))
      (node (ref "D2") (pin "1") (pinfunction "1_1") (pintype "bidirectional"))
      (node (ref "D3") (pin "1") (pinfunction "1_1") (pintype "bidirectional"))
      (node (ref "D4") (pin "1") (pinfunction "1_1") (pintype "bidirectional"))
      (node (ref "D5") (pin "1") (pinfunction "1_1") (pintype "bidirectional"))
      (node (ref "D6") (pin "1") (pinfunction "1_1") (pintype "bidirectional"))
      (node (ref "IC1") (pin "1") (pinfunction "VSS_1") (pintype "bidirectional"))
      (node (ref "IC2") (pin "8") (pinfunction "GND_8") (pintype "bidirectional"))
      (node (ref "JP7") (pin "2") (pinfunction "2_2") (pintype "bidirectional"))
      (node (ref "LED1") (pin "C") (pinfunction "C_C") (pintype "passive"))
      (node (ref "LED10") (pin "C") (pinfunction "C_C") (pintype "passive"))
      (node (ref "LED11") (pin "C") (pinfunction "C_C") (pintype "passive"))
      (node (ref "LED12") (pin "C") (pinfunction "C_C") (pintype "passive"))
      (node (ref "LED13") (pin "C") (pinfunction "C_C") (pintype "passive"))
      (node (ref "LED14") (pin "C") (pinfunction "C_C") (pintype "passive"))
      (node (ref "LED2") (pin "C") (pinfunction "C_C") (pintype "passive"))
      (node (ref "LED7") (pin "C") (pinfunction "C_C") (pintype "passive"))
      (node (ref "LED8") (pin "C") (pinfunction "C_C") (pintype "passive"))
      (node (ref "LED9") (pin "C") (pinfunction "C_C") (pintype "passive"))
      (node (ref "M1") (pin "10") (pinfunction "GND_10") (pintype "bidirectional"))
      (node (ref "M2") (pin "A-GND") (pinfunction "A-GND_A-GND") (pintype "bidirectional"))
      (node (ref "M2") (pin "B-GND") (pinfunction "B-GND_B-GND") (pintype "bidirectional"))
      (node (ref "M2") (pin "C-GND") (pinfunction "C-GND_C-GND") (pintype "bidirectional"))
      (node (ref "M2") (pin "D-GND") (pinfunction "D-GND_D-GND") (pintype "bidirectional"))
      (node (ref "M2") (pin "GND1") (pinfunction "GND_GND1") (pintype "bidirectional"))
      (node (ref "M2") (pin "USB-GND") (pinfunction "USB-GND_USB-GND") (pintype "bidirectional"))
      (node (ref "R3") (pin "1") (pinfunction "1_1") (pintype "passive"))
      (node (ref "R4") (pin "1") (pinfunction "1_1") (pintype "passive"))
      (node (ref "USB1") (pin "5") (pinfunction "GND_5") (pintype "bidirectional"))
      (node (ref "USB1") (pin "MP1") (pinfunction "MP1_MP1") (pintype "bidirectional"))
      (node (ref "USB1") (pin "MP2") (pinfunction "MP2_MP2") (pintype "bidirectional"))
      (node (ref "USB1") (pin "MP3") (pinfunction "MP3_MP3") (pintype "bidirectional"))
      (node (ref "USB1") (pin "MP4") (pinfunction "MP4_MP4") (pintype "bidirectional"))
      (node (ref "USB2") (pin "4") (pinfunction "GND_4") (pintype "bidirectional"))
      (node (ref "USB2") (pin "MH1") (pinfunction "MH1_MH1") (pintype "bidirectional"))
      (node (ref "USB2") (pin "MH2") (pinfunction "MH2_MH2") (pintype "bidirectional"))
      (node (ref "USB3") (pin "4") (pinfunction "GND_4") (pintype "bidirectional"))
      (node (ref "USB3") (pin "MH1") (pinfunction "MH1_MH1") (pintype "bidirectional"))
      (node (ref "USB3") (pin "MH2") (pinfunction "MH2_MH2") (pintype "bidirectional"))
    )
    (net (code "82") (name "Net-(IC1-REXT)") (class "Default")
      (node (ref "IC1") (pin "14") (pinfunction "REXT_14") (pintype "bidirectional"))
      (node (ref "R3") (pin "2") (pinfunction "2_2") (pintype "passive"))
    )
    (net (code "83") (name "Net-(LED1-PadA)") (class "Default")
      (node (ref "LED1") (pin "A") (pinfunction "A_A") (pintype "passive"))
      (node (ref "R1") (pin "1") (pinfunction "1_1") (pintype "passive"))
    )
    (net (code "84") (name "Net-(LED2-PadA)") (class "Default")
      (node (ref "LED2") (pin "A") (pinfunction "A_A") (pintype "passive"))
      (node (ref "R2") (pin "1") (pinfunction "1_1") (pintype "passive"))
    )
    (net (code "85") (name "Net-(LED3-PadC)") (class "Default")
      (node (ref "LED3") (pin "C") (pinfunction "C_C") (pintype "passive"))
      (node (ref "R4") (pin "2") (pinfunction "2_2") (pintype "passive"))
    )
    (net (code "86") (name "Net-(LED4-PadC)") (class "Default")
      (node (ref "LED4") (pin "C") (pinfunction "C_C") (pintype "passive"))
      (node (ref "LED6") (pin "A") (pinfunction "A_A") (pintype "passive"))
      (node (ref "R5") (pin "2") (pinfunction "2_2") (pintype "passive"))
    )
    (net (code "87") (name "Net-(LED5-PadC)") (class "Default")
      (node (ref "LED5") (pin "C") (pinfunction "C_C") (pintype "passive"))
      (node (ref "R6") (pin "2") (pinfunction "2_2") (pintype "passive"))
    )
    (net (code "88") (name "Net-(LED7-PadA)") (class "Default")
      (node (ref "LED7") (pin "A") (pinfunction "A_A") (pintype "passive"))
      (node (ref "R8") (pin "1") (pinfunction "1_1") (pintype "passive"))
    )
    (net (code "89") (name "Net-(LED8-PadA)") (class "Default")
      (node (ref "LED8") (pin "A") (pinfunction "A_A") (pintype "passive"))
      (node (ref "R9") (pin "1") (pinfunction "1_1") (pintype "passive"))
    )
    (net (code "90") (name "Net-(LED9-PadA)") (class "Default")
      (node (ref "LED9") (pin "A") (pinfunction "A_A") (pintype "passive"))
      (node (ref "R10") (pin "1") (pinfunction "1_1") (pintype "passive"))
    )
    (net (code "91") (name "Net-(LED10-PadA)") (class "Default")
      (node (ref "LED10") (pin "A") (pinfunction "A_A") (pintype "passive"))
      (node (ref "R11") (pin "1") (pinfunction "1_1") (pintype "passive"))
    )
    (net (code "92") (name "Net-(LED11-PadA)") (class "Default")
      (node (ref "LED11") (pin "A") (pinfunction "A_A") (pintype "passive"))
      (node (ref "R12") (pin "1") (pinfunction "1_1") (pintype "passive"))
    )
    (net (code "93") (name "Net-(LED12-PadA)") (class "Default")
      (node (ref "LED12") (pin "A") (pinfunction "A_A") (pintype "passive"))
      (node (ref "R13") (pin "1") (pinfunction "1_1") (pintype "passive"))
    )
    (net (code "94") (name "Net-(LED13-PadA)") (class "Default")
      (node (ref "LED13") (pin "A") (pinfunction "A_A") (pintype "passive"))
      (node (ref "R14") (pin "1") (pinfunction "1_1") (pintype "passive"))
    )
    (net (code "95") (name "Net-(LED14-PadA)") (class "Default")
      (node (ref "LED14") (pin "A") (pinfunction "A_A") (pintype "passive"))
      (node (ref "R15") (pin "1") (pinfunction "1_1") (pintype "passive"))
    )
    (net (code "96") (name "Net-(M1-AP_CS)") (class "Default")
      (node (ref "JP8") (pin "1") (pinfunction "1_1") (pintype "bidirectional"))
      (node (ref "JP9") (pin "1") (pinfunction "1_1") (pintype "bidirectional"))
      (node (ref "M1") (pin "6") (pinfunction "AP_CS_6") (pintype "bidirectional"))
    )
    (net (code "97") (name "Net-(M1-AP_SCL{slash}SCLK)") (class "Default")
      (node (ref "JP1") (pin "1") (pinfunction "1_1") (pintype "bidirectional"))
      (node (ref "JP2") (pin "1") (pinfunction "1_1") (pintype "bidirectional"))
      (node (ref "M1") (pin "3") (pinfunction "AP_SCL/SCLK_3") (pintype "bidirectional"))
    )
    (net (code "98") (name "Net-(M1-AP_SDA{slash}SDI)") (class "Default")
      (node (ref "JP3") (pin "1") (pinfunction "1_1") (pintype "bidirectional"))
      (node (ref "JP4") (pin "1") (pinfunction "1_1") (pintype "bidirectional"))
      (node (ref "M1") (pin "4") (pinfunction "AP_SDA/SDI_4") (pintype "bidirectional"))
    )
    (net (code "99") (name "Net-(M1-AP_SDO{slash}AD0)") (class "Default")
      (node (ref "JP5") (pin "1") (pinfunction "1_1") (pintype "bidirectional"))
      (node (ref "JP6") (pin "1") (pinfunction "1_1") (pintype "bidirectional"))
      (node (ref "JP7") (pin "1") (pinfunction "1_1") (pintype "bidirectional"))
      (node (ref "M1") (pin "5") (pinfunction "AP_SDO/AD0_5") (pintype "bidirectional"))
    )
    (net (code "100") (name "Net-(USB2-5V)") (class "Default")
      (node (ref "C8") (pin "1") (pinfunction "1_1") (pintype "passive"))
      (node (ref "FL2") (pin "1") (pinfunction "1_1") (pintype "bidirectional"))
      (node (ref "USB2") (pin "1") (pinfunction "5V_1") (pintype "bidirectional"))
    )
    (net (code "101") (name "Net-(USB3-5V)") (class "Default")
      (node (ref "C9") (pin "1") (pinfunction "1_1") (pintype "passive"))
      (node (ref "FL3") (pin "1") (pinfunction "1_1") (pintype "bidirectional"))
      (node (ref "USB3") (pin "1") (pinfunction "5V_1") (pintype "bidirectional"))
    )
    (net (code "102") (name "unconnected-(IC1-DM4-Pad4)") (class "Default")
      (node (ref "IC1") (pin "4") (pinfunction "DM4_4") (pintype "bidirectional"))
    )
    (net (code "103") (name "unconnected-(IC1-DP4-Pad5)") (class "Default")
      (node (ref "IC1") (pin "5") (pinfunction "DP4_5") (pintype "bidirectional"))
    )
    (net (code "104") (name "unconnected-(IC1-PWRJ-Pad25)") (class "Default")
      (node (ref "IC1") (pin "25") (pinfunction "PWRJ_25") (pintype "bidirectional"))
    )
    (net (code "105") (name "unconnected-(IC1-TESTJ-Pad27)") (class "Default")
      (node (ref "IC1") (pin "27") (pinfunction "TESTJ_27") (pintype "bidirectional"))
    )
    (net (code "106") (name "unconnected-(IC2-QH'-Pad9)") (class "Default")
      (node (ref "IC2") (pin "9") (pinfunction "QH'_9") (pintype "bidirectional"))
    )
    (net (code "107") (name "unconnected-(M1-INT1{slash}INT-Pad9)") (class "Default")
      (node (ref "M1") (pin "9") (pinfunction "INT1/INT_9") (pintype "bidirectional"))
    )
    (net (code "108") (name "unconnected-(M1-INT2{slash}FSYNC{slash}CLKIN-Pad11)") (class "Default")
      (node (ref "M1") (pin "11") (pinfunction "INT2/FSYNC/CLKIN_11") (pintype "bidirectional"))
    )
    (net (code "109") (name "unconnected-(M1-NC1-Pad7)") (class "Default")
      (node (ref "M1") (pin "7") (pinfunction "NC1_7") (pintype "no_connect"))
    )
    (net (code "110") (name "unconnected-(M1-NC2-Pad8)") (class "Default")
      (node (ref "M1") (pin "8") (pinfunction "NC2_8") (pintype "no_connect"))
    )
    (net (code "111") (name "unconnected-(M2-B-3V3-PadB-3.3V)") (class "Default")
      (node (ref "M2") (pin "B-3.3V") (pinfunction "B-3V3_B-3.3V") (pintype "bidirectional"))
    )
    (net (code "112") (name "unconnected-(M2-Pad3V3)") (class "Default")
      (node (ref "M2") (pin "3V3") (pinfunction "3V3_3V3") (pintype "bidirectional"))
    )
    (net (code "113") (name "unconnected-(M2-PadA-3V3)") (class "Default")
      (node (ref "M2") (pin "A-3V3") (pinfunction "A-3V3_A-3V3") (pintype "bidirectional"))
    )
    (net (code "114") (name "unconnected-(M2-PadC-3V3)") (class "Default")
      (node (ref "M2") (pin "C-3V3") (pinfunction "C-3V3_C-3V3") (pintype "bidirectional"))
    )
    (net (code "115") (name "unconnected-(M2-PadD-3V3)") (class "Default")
      (node (ref "M2") (pin "D-3V3") (pinfunction "D-3V3_D-3V3") (pintype "bidirectional"))
    )
    (net (code "116") (name "unconnected-(USB1-ID-Pad4)") (class "Default")
      (node (ref "USB1") (pin "4") (pinfunction "ID_4") (pintype "bidirectional"))
    )
  )
)
